# BL.net
KiCad netlist of a schematic drawn in EAGLE
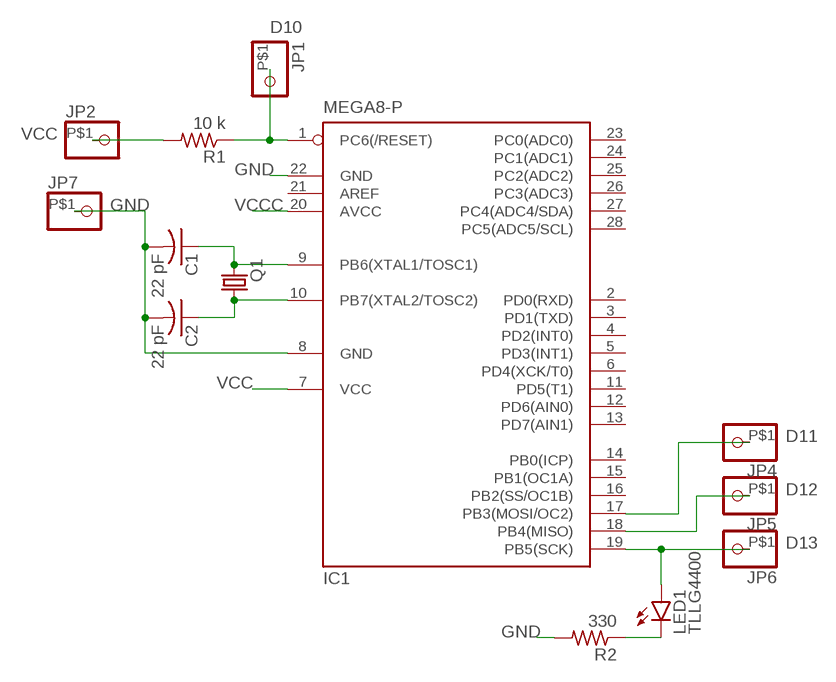
[diagram p0: schematic, sheet 1]

(export (version "E")
  (design (tool "Eeschema 10.0.6"))
  (components
    (comp (ref "C1")
      (value "22 pF")
      (footprint "eagle-import:C025-030X050")
      (libsource (lib "eagle-import") (part "C-US025-030X050"))
    )
    (comp (ref "C2")
      (value "22 pF")
      (footprint "eagle-import:C025-030X050")
      (libsource (lib "eagle-import") (part "C-US025-030X050"))
    )
    (comp (ref "IC1")
      (value "MEGA8-P")
      (footprint "eagle-import:DIL28-3")
      (libsource (lib "eagle-import") (part "MEGA8-P"))
    )
    (comp (ref "JP1")
      (value "PINHD-1X1-BIGPOGO")
      (footprint "eagle-import:1X1-BIGPOGO")
      (libsource (lib "eagle-import") (part "PINHD-1X1-BIGPOGO"))
    )
    (comp (ref "JP2")
      (value "PINHD-1X1-BIGPOGO")
      (footprint "eagle-import:1X1-BIGPOGO")
      (libsource (lib "eagle-import") (part "PINHD-1X1-BIGPOGO"))
    )
    (comp (ref "JP4")
      (value "PINHD-1X1-BIGPOGO")
      (footprint "eagle-import:1X1-BIGPOGO")
      (libsource (lib "eagle-import") (part "PINHD-1X1-BIGPOGO"))
    )
    (comp (ref "JP5")
      (value "PINHD-1X1-BIGPOGO")
      (footprint "eagle-import:1X1-BIGPOGO")
      (libsource (lib "eagle-import") (part "PINHD-1X1-BIGPOGO"))
    )
    (comp (ref "JP6")
      (value "PINHD-1X1-BIGPOGO")
      (footprint "eagle-import:1X1-BIGPOGO")
      (libsource (lib "eagle-import") (part "PINHD-1X1-BIGPOGO"))
    )
    (comp (ref "JP7")
      (value "PINHD-1X1-BIGPOGO")
      (footprint "eagle-import:1X1-BIGPOGO")
      (libsource (lib "eagle-import") (part "PINHD-1X1-BIGPOGO"))
    )
    (comp (ref "LED1")
      (value "TLLG4400")
      (footprint "eagle-import:LED3MM")
      (fields (field (name "MF") "VISHAY SEMICONDUCTOR"))
      (libsource (lib "eagle-import") (part "TLLG4400"))
    )
    (comp (ref "Q1")
      (value "CRYSTALHC49S")
      (footprint "eagle-import:HC49_S")
      (libsource (lib "eagle-import") (part "CRYSTALHC49S"))
    )
    (comp (ref "R1")
      (value "10 k")
      (footprint "eagle-import:0204_7")
      (libsource (lib "eagle-import") (part "R-US_0204/7"))
    )
    (comp (ref "R2")
      (value "330")
      (footprint "eagle-import:0204_7")
      (libsource (lib "eagle-import") (part "R-US_0204/7"))
    )
  )
  (nets
    (net (code "1") (name "/D10") (class "Default")
      (node (ref "IC1") (pin "1") (pinfunction "PC6(/RESET)_1") (pintype "bidirectional"))
      (node (ref "JP1") (pin "P$1") (pinfunction "1_P$1") (pintype "passive"))
      (node (ref "R1") (pin "1") (pinfunction "1_1") (pintype "passive"))
    )
    (net (code "2") (name "/D11") (class "Default")
      (node (ref "IC1") (pin "17") (pinfunction "PB3(MOSI/OC2)_17") (pintype "bidirectional"))
      (node (ref "JP4") (pin "P$1") (pinfunction "1_P$1") (pintype "passive"))
    )
    (net (code "3") (name "/D12") (class "Default")
      (node (ref "IC1") (pin "18") (pinfunction "PB4(MISO)_18") (pintype "bidirectional"))
      (node (ref "JP5") (pin "P$1") (pinfunction "1_P$1") (pintype "passive"))
    )
    (net (code "4") (name "/D13") (class "Default")
      (node (ref "IC1") (pin "19") (pinfunction "PB5(SCK)_19") (pintype "bidirectional"))
      (node (ref "JP6") (pin "P$1") (pinfunction "1_P$1") (pintype "passive"))
      (node (ref "LED1") (pin "A") (pinfunction "A_A") (pintype "passive"))
    )
    (net (code "5") (name "/GND") (class "Default")
      (node (ref "C1") (pin "2") (pinfunction "2_2") (pintype "passive"))
      (node (ref "C2") (pin "2") (pinfunction "2_2") (pintype "passive"))
      (node (ref "IC1") (pin "22") (pinfunction "GND_22") (pintype "power_in"))
      (node (ref "IC1") (pin "8") (pinfunction "GND_8") (pintype "power_in"))
      (node (ref "JP7") (pin "P$1") (pinfunction "1_P$1") (pintype "passive"))
      (node (ref "R2") (pin "2") (pinfunction "2_2") (pintype "passive"))
    )
    (net (code "6") (name "/VCC") (class "Default")
      (node (ref "IC1") (pin "7") (pinfunction "VCC_7") (pintype "power_in"))
      (node (ref "JP2") (pin "P$1") (pinfunction "1_P$1") (pintype "passive"))
      (node (ref "R1") (pin "2") (pinfunction "2_2") (pintype "passive"))
    )
    (net (code "7") (name "/VCCC") (class "Default")
      (node (ref "IC1") (pin "20") (pinfunction "AVCC_20") (pintype "power_in"))
    )
    (net (code "8") (name "Net-(IC1-PB6(XTAL1{slash}TOSC1))") (class "Default")
      (node (ref "C1") (pin "1") (pinfunction "1_1") (pintype "passive"))
      (node (ref "IC1") (pin "9") (pinfunction "PB6(XTAL1/TOSC1)_9") (pintype "bidirectional"))
      (node (ref "Q1") (pin "2") (pinfunction "2_2") (pintype "passive"))
    )
    (net (code "9") (name "Net-(IC1-PB7(XTAL2{slash}TOSC2))") (class "Default")
      (node (ref "C2") (pin "1") (pinfunction "1_1") (pintype "passive"))
      (node (ref "IC1") (pin "10") (pinfunction "PB7(XTAL2/TOSC2)_10") (pintype "bidirectional"))
      (node (ref "Q1") (pin "1") (pinfunction "1_1") (pintype "passive"))
    )
    (net (code "10") (name "Net-(LED1-C)") (class "Default")
      (node (ref "LED1") (pin "K") (pinfunction "C_K") (pintype "passive"))
      (node (ref "R2") (pin "1") (pinfunction "1_1") (pintype "passive"))
    )
    (net (code "11") (name "unconnected-(IC1-AREF-Pad21)") (class "Default")
      (node (ref "IC1") (pin "21") (pinfunction "AREF_21") (pintype "passive"))
    )
    (net (code "12") (name "unconnected-(IC1-PB0(ICP)-Pad14)") (class "Default")
      (node (ref "IC1") (pin "14") (pinfunction "PB0(ICP)_14") (pintype "bidirectional"))
    )
    (net (code "13") (name "unconnected-(IC1-PB1(OC1A)-Pad15)") (class "Default")
      (node (ref "IC1") (pin "15") (pinfunction "PB1(OC1A)_15") (pintype "bidirectional"))
    )
    (net (code "14") (name "unconnected-(IC1-PB2(SS{slash}OC1B)-Pad16)") (class "Default")
      (node (ref "IC1") (pin "16") (pinfunction "PB2(SS/OC1B)_16") (pintype "bidirectional"))
    )
    (net (code "15") (name "unconnected-(IC1-PC0(ADC0)-Pad23)") (class "Default")
      (node (ref "IC1") (pin "23") (pinfunction "PC0(ADC0)_23") (pintype "bidirectional"))
    )
    (net (code "16") (name "unconnected-(IC1-PC1(ADC1)-Pad24)") (class "Default")
      (node (ref "IC1") (pin "24") (pinfunction "PC1(ADC1)_24") (pintype "bidirectional"))
    )
    (net (code "17") (name "unconnected-(IC1-PC2(ADC2)-Pad25)") (class "Default")
      (node (ref "IC1") (pin "25") (pinfunction "PC2(ADC2)_25") (pintype "bidirectional"))
    )
    (net (code "18") (name "unconnected-(IC1-PC3(ADC3)-Pad26)") (class "Default")
      (node (ref "IC1") (pin "26") (pinfunction "PC3(ADC3)_26") (pintype "bidirectional"))
    )
    (net (code "19") (name "unconnected-(IC1-PC4(ADC4{slash}SDA)-Pad27)") (class "Default")
      (node (ref "IC1") (pin "27") (pinfunction "PC4(ADC4/SDA)_27") (pintype "bidirectional"))
    )
    (net (code "20") (name "unconnected-(IC1-PC5(ADC5{slash}SCL)-Pad28)") (class "Default")
      (node (ref "IC1") (pin "28") (pinfunction "PC5(ADC5/SCL)_28") (pintype "bidirectional"))
    )
    (net (code "21") (name "unconnected-(IC1-PD0(RXD)-Pad2)") (class "Default")
      (node (ref "IC1") (pin "2") (pinfunction "PD0(RXD)_2") (pintype "bidirectional"))
    )
    (net (code "22") (name "unconnected-(IC1-PD1(TXD)-Pad3)") (class "Default")
      (node (ref "IC1") (pin "3") (pinfunction "PD1(TXD)_3") (pintype "bidirectional"))
    )
    (net (code "23") (name "unconnected-(IC1-PD2(INT0)-Pad4)") (class "Default")
      (node (ref "IC1") (pin "4") (pinfunction "PD2(INT0)_4") (pintype "bidirectional"))
    )
    (net (code "24") (name "unconnected-(IC1-PD3(INT1)-Pad5)") (class "Default")
      (node (ref "IC1") (pin "5") (pinfunction "PD3(INT1)_5") (pintype "bidirectional"))
    )
    (net (code "25") (name "unconnected-(IC1-PD4(XCK{slash}T0)-Pad6)") (class "Default")
      (node (ref "IC1") (pin "6") (pinfunction "PD4(XCK/T0)_6") (pintype "bidirectional"))
    )
    (net (code "26") (name "unconnected-(IC1-PD5(T1)-Pad11)") (class "Default")
      (node (ref "IC1") (pin "11") (pinfunction "PD5(T1)_11") (pintype "bidirectional"))
    )
    (net (code "27") (name "unconnected-(IC1-PD6(AIN0)-Pad12)") (class "Default")
      (node (ref "IC1") (pin "12") (pinfunction "PD6(AIN0)_12") (pintype "bidirectional"))
    )
    (net (code "28") (name "unconnected-(IC1-PD7(AIN1)-Pad13)") (class "Default")
      (node (ref "IC1") (pin "13") (pinfunction "PD7(AIN1)_13") (pintype "bidirectional"))
    )
  )
)
